# Motor_Control.net
KiCad netlist of a schematic drawn in Altium Designer
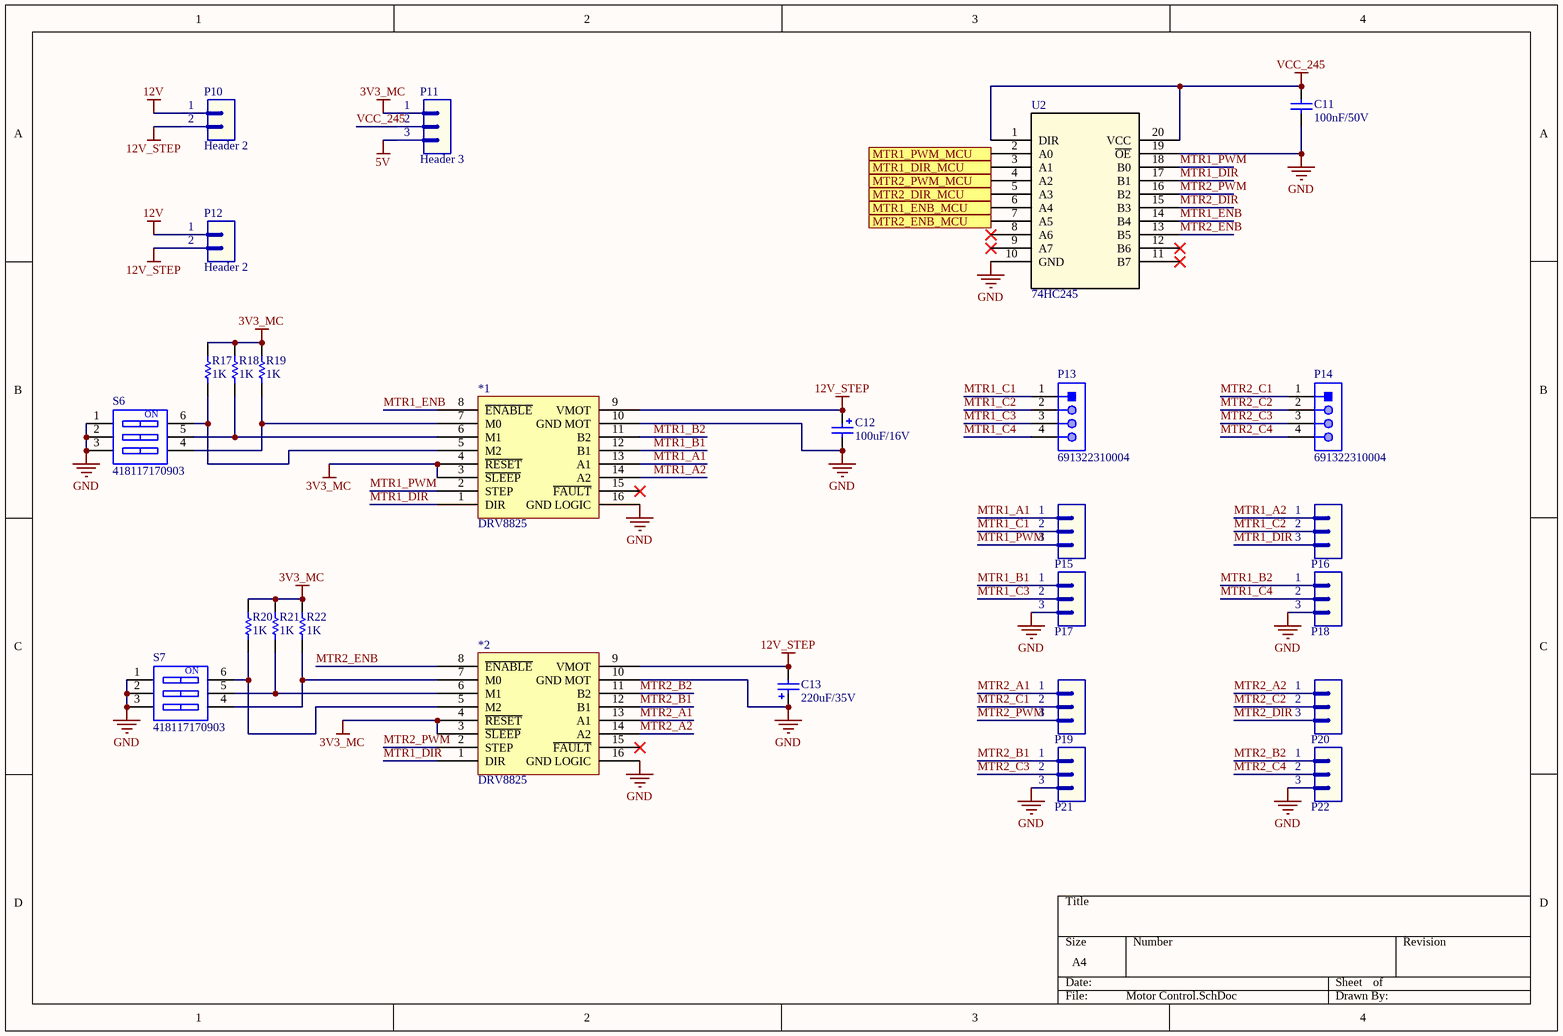
[diagram p0: Motor Control.SchDoc]

(export (version "E")
  (design (tool "Eeschema 10.0.6"))
  (components
    (comp (ref "*1")
      (value "DRV8825")
      (footprint "DRV8825")
      (libsource (lib "Integrated_Library") (part "DRV8825"))
    )
    (comp (ref "*2")
      (value "DRV8825")
      (footprint "DRV8825")
      (libsource (lib "Integrated_Library") (part "DRV8825"))
    )
    (comp (ref "C11")
      (value "100nF/50V")
      (footprint "CAP-SM-0805")
      (description "CAP CER 10UF 50V X5R 0805")
      (fields
        (field (name "MANUFACTURER") "Yageo")
        (field (name "MANUFACTURER PART NUMBER") "CC0805KKX5R9BB106")
      )
      (libsource (lib "Capacitor") (part "Cap-10uF-50V-0805"))
    )
    (comp (ref "C12")
      (value "100uF/16V")
      (footprint "CAP-SM-AL-SIZE-D-D6L6")
      (description "CAP ALUM 100UF 20% 16V SMD")
      (fields
        (field (name "MANUFACTURER") "Nichicon")
        (field (name "MANUFACTURER PART NUMBER") "UWX1C101MCL1GB")
      )
      (libsource (lib "Capacitor") (part "Cap-Al-100uF-16V-D6L5"))
    )
    (comp (ref "C13")
      (value "220uF/35V")
      (footprint "CAP-SM-AL-SIZE-F-D8L10")
      (description "CAP ALUM 220UF 20% 35V SMD")
      (fields
        (field (name "MANUFACTURER") "Nichicon")
        (field (name "MANUFACTURER PART NUMBER") "UWT1V221MNL1GS")
      )
      (libsource (lib "Capacitor") (part "Cap-Al-220uF-35V-D8L10"))
    )
    (comp (ref "P10")
      (value "Header 2")
      (footprint "JP2")
      (description "Header, 2-Pin")
      (fields (field (name "PUBLISHER") "Altium Limited"))
      (libsource (lib "PIF_C16_lib") (part "Header 2"))
    )
    (comp (ref "P11")
      (value "Header 3")
      (footprint "JP3")
      (description "Header, 3-Pin")
      (fields (field (name "PUBLISHER") "Altium Limited"))
      (libsource (lib "PIF_C16_lib") (part "Header 3"))
    )
    (comp (ref "P12")
      (value "Header 2")
      (footprint "JP2")
      (description "Header, 2-Pin")
      (fields (field (name "PUBLISHER") "Altium Limited"))
      (libsource (lib "PIF_C16_lib") (part "Header 2"))
    )
    (comp (ref "P13")
      (value "691322310004")
      (footprint "691322310004")
      (description "WR-TBL Serie 322 Horizontal PCB Header, Pluggable, pitch 3.81mm, 4p")
      (fields (field (name "PUBLISHER") "Wurth Elektronik"))
      (libsource (lib "691101710002_Altium_WR-TBL_rev19a") (part "691322310004"))
    )
    (comp (ref "P14")
      (value "691322310004")
      (footprint "691322310004")
      (description "WR-TBL Serie 322 Horizontal PCB Header, Pluggable, pitch 3.81mm, 4p")
      (fields (field (name "PUBLISHER") "Wurth Elektronik"))
      (libsource (lib "691101710002_Altium_WR-TBL_rev19a") (part "691322310004"))
    )
    (comp (ref "P15")
      (value "Header 3")
      (footprint "JP3")
      (description "Header, 3-Pin")
      (fields (field (name "PUBLISHER") "Altium Limited"))
      (libsource (lib "Header-connector") (part "Header 3"))
    )
    (comp (ref "P16")
      (value "Header 3")
      (footprint "JP3")
      (description "Header, 3-Pin")
      (fields (field (name "PUBLISHER") "Altium Limited"))
      (libsource (lib "Header-connector") (part "Header 3"))
    )
    (comp (ref "P17")
      (value "Header 3")
      (footprint "JP3")
      (description "Header, 3-Pin")
      (fields (field (name "PUBLISHER") "Altium Limited"))
      (libsource (lib "Header-connector") (part "Header 3"))
    )
    (comp (ref "P18")
      (value "Header 3")
      (footprint "JP3")
      (description "Header, 3-Pin")
      (fields (field (name "PUBLISHER") "Altium Limited"))
      (libsource (lib "Header-connector") (part "Header 3"))
    )
    (comp (ref "P19")
      (value "Header 3")
      (footprint "JP3")
      (description "Header, 3-Pin")
      (fields (field (name "PUBLISHER") "Altium Limited"))
      (libsource (lib "Header-connector") (part "Header 3"))
    )
    (comp (ref "P20")
      (value "Header 3")
      (footprint "JP3")
      (description "Header, 3-Pin")
      (fields (field (name "PUBLISHER") "Altium Limited"))
      (libsource (lib "Header-connector") (part "Header 3"))
    )
    (comp (ref "P21")
      (value "Header 3")
      (footprint "JP3")
      (description "Header, 3-Pin")
      (fields (field (name "PUBLISHER") "Altium Limited"))
      (libsource (lib "Header-connector") (part "Header 3"))
    )
    (comp (ref "P22")
      (value "Header 3")
      (footprint "JP3")
      (description "Header, 3-Pin")
      (fields (field (name "PUBLISHER") "Altium Limited"))
      (libsource (lib "Header-connector") (part "Header 3"))
    )
    (comp (ref "R17")
      (value "1K")
      (footprint "Resistor:RES-SM-0805")
      (description "RES 1K OHM 1% 1/4W 0805")
      (fields
        (field (name "MANUFACTURER") "Stackpole Electronics Inc")
        (field (name "MANUFACTURER PART NUMBER") "RNCP0805FTD1K00")
      )
      (libsource (lib "Resistor") (part "Res-1K-0805"))
    )
    (comp (ref "R18")
      (value "1K")
      (footprint "Resistor:RES-SM-0805")
      (description "RES 1K OHM 1% 1/4W 0805")
      (fields
        (field (name "MANUFACTURER") "Stackpole Electronics Inc")
        (field (name "MANUFACTURER PART NUMBER") "RNCP0805FTD1K00")
      )
      (libsource (lib "Resistor") (part "Res-1K-0805"))
    )
    (comp (ref "R19")
      (value "1K")
      (footprint "Resistor:RES-SM-0805")
      (description "RES 1K OHM 1% 1/4W 0805")
      (fields
        (field (name "MANUFACTURER") "Stackpole Electronics Inc")
        (field (name "MANUFACTURER PART NUMBER") "RNCP0805FTD1K00")
      )
      (libsource (lib "Resistor") (part "Res-1K-0805"))
    )
    (comp (ref "R20")
      (value "1K")
      (footprint "Resistor:RES-SM-0805")
      (description "RES 1K OHM 1% 1/4W 0805")
      (fields
        (field (name "MANUFACTURER") "Stackpole Electronics Inc")
        (field (name "MANUFACTURER PART NUMBER") "RNCP0805FTD1K00")
      )
      (libsource (lib "Resistor") (part "Res-1K-0805"))
    )
    (comp (ref "R21")
      (value "1K")
      (footprint "Resistor:RES-SM-0805")
      (description "RES 1K OHM 1% 1/4W 0805")
      (fields
        (field (name "MANUFACTURER") "Stackpole Electronics Inc")
        (field (name "MANUFACTURER PART NUMBER") "RNCP0805FTD1K00")
      )
      (libsource (lib "Resistor") (part "Res-1K-0805"))
    )
    (comp (ref "R22")
      (value "1K")
      (footprint "Resistor:RES-SM-0805")
      (description "RES 1K OHM 1% 1/4W 0805")
      (fields
        (field (name "MANUFACTURER") "Stackpole Electronics Inc")
        (field (name "MANUFACTURER PART NUMBER") "RNCP0805FTD1K00")
      )
      (libsource (lib "Resistor") (part "Res-1K-0805"))
    )
    (comp (ref "S6")
      (value "418117170903")
      (footprint "418117170903")
      (description "WS-DITV Compact THT Dip Switch, Flat Actuator, pitch 2.54mm, 3p")
      (fields (field (name "PUBLISHER") "Wurth Elektronik"))
      (libsource (lib "418117170903_Altium_WS-DITV_rev19a") (part "418117170903"))
    )
    (comp (ref "S7")
      (value "418117170903")
      (footprint "418117170903")
      (description "WS-DITV Compact THT Dip Switch, Flat Actuator, pitch 2.54mm, 3p")
      (fields (field (name "PUBLISHER") "Wurth Elektronik"))
      (libsource (lib "418117170903_Altium_WS-DITV_rev19a") (part "418117170903"))
    )
    (comp (ref "U2")
      (value "74HC245")
      (footprint "74HC245,625")
      (description "No Description Available")
      (fields (field (name "COPYRIGHT") "Copyright (C) 2018 Accelerated Designs. All rights reserved"))
      (libsource (lib "Integrated_Library") (part "74HC245"))
    )
  )
  (nets
    (net (code "1") (name "/MTR1_A1") (class "Default")
      (node (ref "*1") (pin "13") (pinfunction "A1_13") (pintype "passive"))
      (node (ref "P15") (pin "1") (pinfunction "1_1") (pintype "passive"))
    )
    (net (code "2") (name "/MTR1_A2") (class "Default")
      (node (ref "*1") (pin "14") (pinfunction "A2_14") (pintype "passive"))
      (node (ref "P16") (pin "1") (pinfunction "1_1") (pintype "passive"))
    )
    (net (code "3") (name "/MTR1_B1") (class "Default")
      (node (ref "*1") (pin "12") (pinfunction "B1_12") (pintype "passive"))
      (node (ref "P17") (pin "1") (pinfunction "1_1") (pintype "passive"))
    )
    (net (code "4") (name "/MTR1_B2") (class "Default")
      (node (ref "*1") (pin "11") (pinfunction "B2_11") (pintype "passive"))
      (node (ref "P18") (pin "1") (pinfunction "1_1") (pintype "passive"))
    )
    (net (code "5") (name "/MTR1_C1") (class "Default")
      (node (ref "P13") (pin "1") (pinfunction "1_1") (pintype "passive"))
      (node (ref "P15") (pin "2") (pinfunction "2_2") (pintype "passive"))
    )
    (net (code "6") (name "/MTR1_C2") (class "Default")
      (node (ref "P13") (pin "2") (pinfunction "2_2") (pintype "passive"))
      (node (ref "P16") (pin "2") (pinfunction "2_2") (pintype "passive"))
    )
    (net (code "7") (name "/MTR1_C3") (class "Default")
      (node (ref "P13") (pin "3") (pinfunction "3_3") (pintype "passive"))
      (node (ref "P17") (pin "2") (pinfunction "2_2") (pintype "passive"))
    )
    (net (code "8") (name "/MTR1_C4") (class "Default")
      (node (ref "P13") (pin "4") (pinfunction "4_4") (pintype "passive"))
      (node (ref "P18") (pin "2") (pinfunction "2_2") (pintype "passive"))
    )
    (net (code "9") (name "/MTR1_DIR") (class "Default")
      (node (ref "*1") (pin "1") (pinfunction "DIR_1") (pintype "passive"))
      (node (ref "*2") (pin "1") (pinfunction "DIR_1") (pintype "passive"))
      (node (ref "P16") (pin "3") (pinfunction "3_3") (pintype "passive"))
      (node (ref "U2") (pin "17") (pinfunction "B1_17") (pintype "passive"))
    )
    (net (code "10") (name "/MTR1_DIR_MCU") (class "Default")
      (node (ref "U2") (pin "3") (pinfunction "A1_3") (pintype "passive"))
    )
    (net (code "11") (name "/MTR1_ENB") (class "Default")
      (node (ref "*1") (pin "8") (pinfunction "~{ENABLE}_8") (pintype "passive"))
      (node (ref "U2") (pin "14") (pinfunction "B4_14") (pintype "passive"))
    )
    (net (code "12") (name "/MTR1_ENB_MCU") (class "Default")
      (node (ref "U2") (pin "6") (pinfunction "A4_6") (pintype "passive"))
    )
    (net (code "13") (name "/MTR1_PWM") (class "Default")
      (node (ref "*1") (pin "2") (pinfunction "STEP_2") (pintype "passive"))
      (node (ref "P15") (pin "3") (pinfunction "3_3") (pintype "passive"))
      (node (ref "U2") (pin "18") (pinfunction "B0_18") (pintype "passive"))
    )
    (net (code "14") (name "/MTR1_PWM_MCU") (class "Default")
      (node (ref "U2") (pin "2") (pinfunction "A0_2") (pintype "passive"))
    )
    (net (code "15") (name "/MTR2_A1") (class "Default")
      (node (ref "*2") (pin "13") (pinfunction "A1_13") (pintype "passive"))
      (node (ref "P19") (pin "1") (pinfunction "1_1") (pintype "passive"))
    )
    (net (code "16") (name "/MTR2_A2") (class "Default")
      (node (ref "*2") (pin "14") (pinfunction "A2_14") (pintype "passive"))
      (node (ref "P20") (pin "1") (pinfunction "1_1") (pintype "passive"))
    )
    (net (code "17") (name "/MTR2_B1") (class "Default")
      (node (ref "*2") (pin "12") (pinfunction "B1_12") (pintype "passive"))
      (node (ref "P21") (pin "1") (pinfunction "1_1") (pintype "passive"))
    )
    (net (code "18") (name "/MTR2_B2") (class "Default")
      (node (ref "*2") (pin "11") (pinfunction "B2_11") (pintype "passive"))
      (node (ref "P22") (pin "1") (pinfunction "1_1") (pintype "passive"))
    )
    (net (code "19") (name "/MTR2_C1") (class "Default")
      (node (ref "P14") (pin "1") (pinfunction "1_1") (pintype "passive"))
      (node (ref "P19") (pin "2") (pinfunction "2_2") (pintype "passive"))
    )
    (net (code "20") (name "/MTR2_C2") (class "Default")
      (node (ref "P14") (pin "2") (pinfunction "2_2") (pintype "passive"))
      (node (ref "P20") (pin "2") (pinfunction "2_2") (pintype "passive"))
    )
    (net (code "21") (name "/MTR2_C3") (class "Default")
      (node (ref "P14") (pin "3") (pinfunction "3_3") (pintype "passive"))
      (node (ref "P21") (pin "2") (pinfunction "2_2") (pintype "passive"))
    )
    (net (code "22") (name "/MTR2_C4") (class "Default")
      (node (ref "P14") (pin "4") (pinfunction "4_4") (pintype "passive"))
      (node (ref "P22") (pin "2") (pinfunction "2_2") (pintype "passive"))
    )
    (net (code "23") (name "/MTR2_DIR") (class "Default")
      (node (ref "P20") (pin "3") (pinfunction "3_3") (pintype "passive"))
      (node (ref "U2") (pin "15") (pinfunction "B3_15") (pintype "passive"))
    )
    (net (code "24") (name "/MTR2_DIR_MCU") (class "Default")
      (node (ref "U2") (pin "5") (pinfunction "A3_5") (pintype "passive"))
    )
    (net (code "25") (name "/MTR2_ENB") (class "Default")
      (node (ref "*2") (pin "8") (pinfunction "~{ENABLE}_8") (pintype "passive"))
      (node (ref "U2") (pin "13") (pinfunction "B5_13") (pintype "passive"))
    )
    (net (code "26") (name "/MTR2_ENB_MCU") (class "Default")
      (node (ref "U2") (pin "7") (pinfunction "A5_7") (pintype "passive"))
    )
    (net (code "27") (name "/MTR2_PWM") (class "Default")
      (node (ref "*2") (pin "2") (pinfunction "STEP_2") (pintype "passive"))
      (node (ref "P19") (pin "3") (pinfunction "3_3") (pintype "passive"))
      (node (ref "U2") (pin "16") (pinfunction "B2_16") (pintype "passive"))
    )
    (net (code "28") (name "/MTR2_PWM_MCU") (class "Default")
      (node (ref "U2") (pin "4") (pinfunction "A2_4") (pintype "passive"))
    )
    (net (code "29") (name "3V3_MC") (class "Default")
      (node (ref "*1") (pin "3") (pinfunction "~{SLEEP}_3") (pintype "passive"))
      (node (ref "*1") (pin "4") (pinfunction "~{RESET}_4") (pintype "passive"))
      (node (ref "*2") (pin "3") (pinfunction "~{SLEEP}_3") (pintype "passive"))
      (node (ref "*2") (pin "4") (pinfunction "~{RESET}_4") (pintype "passive"))
      (node (ref "P11") (pin "1") (pinfunction "1_1") (pintype "passive"))
      (node (ref "R17") (pin "2") (pinfunction "2_2") (pintype "passive"))
      (node (ref "R18") (pin "2") (pinfunction "2_2") (pintype "passive"))
      (node (ref "R19") (pin "2") (pinfunction "2_2") (pintype "passive"))
      (node (ref "R20") (pin "2") (pinfunction "2_2") (pintype "passive"))
      (node (ref "R21") (pin "2") (pinfunction "2_2") (pintype "passive"))
      (node (ref "R22") (pin "2") (pinfunction "2_2") (pintype "passive"))
    )
    (net (code "30") (name "5V") (class "Default")
      (node (ref "P11") (pin "3") (pinfunction "3_3") (pintype "passive"))
    )
    (net (code "31") (name "12V") (class "Default")
      (node (ref "P10") (pin "1") (pinfunction "1_1") (pintype "passive"))
      (node (ref "P12") (pin "1") (pinfunction "1_1") (pintype "passive"))
    )
    (net (code "32") (name "12V_STEP") (class "Default")
      (node (ref "*1") (pin "9") (pinfunction "VMOT_9") (pintype "passive"))
      (node (ref "*2") (pin "9") (pinfunction "VMOT_9") (pintype "passive"))
      (node (ref "C12") (pin "1") (pinfunction "1_1") (pintype "passive"))
      (node (ref "C13") (pin "2") (pinfunction "2_2") (pintype "passive"))
      (node (ref "P10") (pin "2") (pinfunction "2_2") (pintype "passive"))
      (node (ref "P12") (pin "2") (pinfunction "2_2") (pintype "passive"))
    )
    (net (code "33") (name "GND") (class "Default")
      (node (ref "*1") (pin "10") (pinfunction "GND_MOT_10") (pintype "passive"))
      (node (ref "*1") (pin "16") (pinfunction "GND_LOGIC_16") (pintype "passive"))
      (node (ref "*2") (pin "10") (pinfunction "GND_MOT_10") (pintype "passive"))
      (node (ref "*2") (pin "16") (pinfunction "GND_LOGIC_16") (pintype "passive"))
      (node (ref "C11") (pin "1") (pinfunction "1_1") (pintype "passive"))
      (node (ref "C12") (pin "2") (pinfunction "2_2") (pintype "passive"))
      (node (ref "C13") (pin "1") (pinfunction "1_1") (pintype "passive"))
      (node (ref "P17") (pin "3") (pinfunction "3_3") (pintype "passive"))
      (node (ref "P18") (pin "3") (pinfunction "3_3") (pintype "passive"))
      (node (ref "P21") (pin "3") (pinfunction "3_3") (pintype "passive"))
      (node (ref "P22") (pin "3") (pinfunction "3_3") (pintype "passive"))
      (node (ref "S6") (pin "1") (pinfunction "1_1") (pintype "passive"))
      (node (ref "S6") (pin "2") (pinfunction "2_2") (pintype "passive"))
      (node (ref "S6") (pin "3") (pinfunction "3_3") (pintype "passive"))
      (node (ref "S7") (pin "1") (pinfunction "1_1") (pintype "passive"))
      (node (ref "S7") (pin "2") (pinfunction "2_2") (pintype "passive"))
      (node (ref "S7") (pin "3") (pinfunction "3_3") (pintype "passive"))
      (node (ref "U2") (pin "10") (pinfunction "GND_10") (pintype "passive"))
      (node (ref "U2") (pin "19") (pinfunction "~{OE}_19") (pintype "passive"))
    )
    (net (code "34") (name "Net-(*1-M0)") (class "Default")
      (node (ref "*1") (pin "7") (pinfunction "M0_7") (pintype "passive"))
      (node (ref "R19") (pin "1") (pinfunction "1_1") (pintype "passive"))
      (node (ref "S6") (pin "4") (pinfunction "4_4") (pintype "passive"))
    )
    (net (code "35") (name "Net-(*1-M1)") (class "Default")
      (node (ref "*1") (pin "6") (pinfunction "M1_6") (pintype "passive"))
      (node (ref "R18") (pin "1") (pinfunction "1_1") (pintype "passive"))
      (node (ref "S6") (pin "5") (pinfunction "5_5") (pintype "passive"))
    )
    (net (code "36") (name "Net-(*1-M2)") (class "Default")
      (node (ref "*1") (pin "5") (pinfunction "M2_5") (pintype "passive"))
      (node (ref "R17") (pin "1") (pinfunction "1_1") (pintype "passive"))
      (node (ref "S6") (pin "6") (pinfunction "6_6") (pintype "passive"))
    )
    (net (code "37") (name "Net-(*2-M0)") (class "Default")
      (node (ref "*2") (pin "7") (pinfunction "M0_7") (pintype "passive"))
      (node (ref "R22") (pin "1") (pinfunction "1_1") (pintype "passive"))
      (node (ref "S7") (pin "4") (pinfunction "4_4") (pintype "passive"))
    )
    (net (code "38") (name "Net-(*2-M1)") (class "Default")
      (node (ref "*2") (pin "6") (pinfunction "M1_6") (pintype "passive"))
      (node (ref "R21") (pin "1") (pinfunction "1_1") (pintype "passive"))
      (node (ref "S7") (pin "5") (pinfunction "5_5") (pintype "passive"))
    )
    (net (code "39") (name "Net-(*2-M2)") (class "Default")
      (node (ref "*2") (pin "5") (pinfunction "M2_5") (pintype "passive"))
      (node (ref "R20") (pin "1") (pinfunction "1_1") (pintype "passive"))
      (node (ref "S7") (pin "6") (pinfunction "6_6") (pintype "passive"))
    )
    (net (code "40") (name "VCC_245") (class "Default")
      (node (ref "C11") (pin "2") (pinfunction "2_2") (pintype "passive"))
      (node (ref "P11") (pin "2") (pinfunction "2_2") (pintype "passive"))
      (node (ref "U2") (pin "1") (pinfunction "DIR_1") (pintype "passive"))
      (node (ref "U2") (pin "20") (pinfunction "VCC_20") (pintype "passive"))
    )
    (net (code "41") (name "unconnected-(*1-~{FAULT}-Pad15)") (class "Default")
      (node (ref "*1") (pin "15") (pinfunction "~{FAULT}_15") (pintype "passive+no_connect"))
    )
    (net (code "42") (name "unconnected-(*2-~{FAULT}-Pad15)") (class "Default")
      (node (ref "*2") (pin "15") (pinfunction "~{FAULT}_15") (pintype "passive+no_connect"))
    )
    (net (code "43") (name "unconnected-(U2-A6-Pad8)") (class "Default")
      (node (ref "U2") (pin "8") (pinfunction "A6_8") (pintype "passive+no_connect"))
    )
    (net (code "44") (name "unconnected-(U2-A7-Pad9)") (class "Default")
      (node (ref "U2") (pin "9") (pinfunction "A7_9") (pintype "passive+no_connect"))
    )
    (net (code "45") (name "unconnected-(U2-B6-Pad12)") (class "Default")
      (node (ref "U2") (pin "12") (pinfunction "B6_12") (pintype "passive+no_connect"))
    )
    (net (code "46") (name "unconnected-(U2-B7-Pad11)") (class "Default")
      (node (ref "U2") (pin "11") (pinfunction "B7_11") (pintype "passive+no_connect"))
    )
  )
)
